# Elektrisch_schema_EasyEDA.net
KiCad netlist of a schematic drawn in EasyEDA
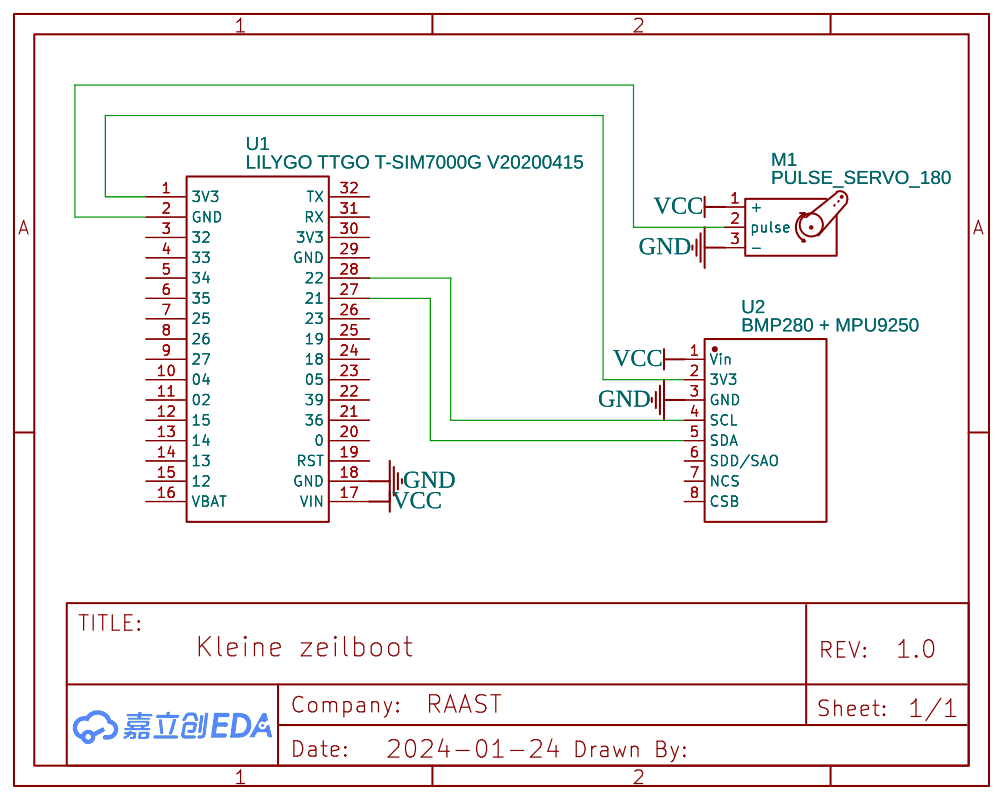
[diagram p0: schematic sheet]

(export (version "E")
  (design (tool "Eeschema 10.0.6"))
  (components
    (comp (ref "M1") (value "PULSE_SERVO_180") (libsource (lib "") (part "PULSE_SERVO_180")))
    (comp (ref "U1")
      (value "LILYGO TTGO T-SIM7000G V20200415")
      (fields (field (name "BOM_Manufacturer Part") "T-SIM7000G"))
      (libsource (lib "") (part "LILYGO TTGO T-SIM7000G V20200415"))
    )
    (comp (ref "U2") (value "BMP280 + MPU9250") (libsource (lib "") (part "BMP280 + MPU9250")))
  )
  (nets
    (net (code "1") (name "GND") (class "Default")
      (node (ref "M1") (pin "3") (pinfunction "-_3") (pintype "unspecified"))
      (node (ref "U1") (pin "18") (pinfunction "GND_18") (pintype "unspecified"))
      (node (ref "U2") (pin "3") (pinfunction "GND_3") (pintype "unspecified"))
    )
    (net (code "2") (name "Net-(M1-pulse)") (class "Default")
      (node (ref "M1") (pin "2") (pinfunction "pulse_2") (pintype "unspecified"))
      (node (ref "U1") (pin "2") (pinfunction "GND_2") (pintype "unspecified"))
    )
    (net (code "3") (name "Net-(U1-21)") (class "Default")
      (node (ref "U1") (pin "27") (pinfunction "21_27") (pintype "unspecified"))
      (node (ref "U2") (pin "5") (pinfunction "SDA_5") (pintype "unspecified"))
    )
    (net (code "4") (name "Net-(U1-22)") (class "Default")
      (node (ref "U1") (pin "28") (pinfunction "22_28") (pintype "unspecified"))
      (node (ref "U2") (pin "4") (pinfunction "SCL_4") (pintype "unspecified"))
    )
    (net (code "5") (name "Net-(U2-3V3)") (class "Default")
      (node (ref "U1") (pin "1") (pinfunction "3V3_1") (pintype "unspecified"))
      (node (ref "U2") (pin "2") (pinfunction "3V3_2") (pintype "unspecified"))
    )
    (net (code "6") (name "VCC") (class "Default")
      (node (ref "M1") (pin "1") (pinfunction "+_1") (pintype "unspecified"))
      (node (ref "U1") (pin "17") (pinfunction "VIN_17") (pintype "unspecified"))
      (node (ref "U2") (pin "1") (pinfunction "Vin_1") (pintype "unspecified"))
    )
    (net (code "7") (name "unconnected-(U1-0-Pad20)") (class "Default")
      (node (ref "U1") (pin "20") (pinfunction "0_20") (pintype "unspecified"))
    )
    (net (code "8") (name "unconnected-(U1-02-Pad11)") (class "Default")
      (node (ref "U1") (pin "11") (pinfunction "02_11") (pintype "unspecified"))
    )
    (net (code "9") (name "unconnected-(U1-3V3-Pad30)") (class "Default")
      (node (ref "U1") (pin "30") (pinfunction "3V3_30") (pintype "unspecified"))
    )
    (net (code "10") (name "unconnected-(U1-04-Pad10)") (class "Default")
      (node (ref "U1") (pin "10") (pinfunction "04_10") (pintype "unspecified"))
    )
    (net (code "11") (name "unconnected-(U1-05-Pad23)") (class "Default")
      (node (ref "U1") (pin "23") (pinfunction "05_23") (pintype "unspecified"))
    )
    (net (code "12") (name "unconnected-(U1-12-Pad15)") (class "Default")
      (node (ref "U1") (pin "15") (pinfunction "12_15") (pintype "unspecified"))
    )
    (net (code "13") (name "unconnected-(U1-13-Pad14)") (class "Default")
      (node (ref "U1") (pin "14") (pinfunction "13_14") (pintype "unspecified"))
    )
    (net (code "14") (name "unconnected-(U1-14-Pad13)") (class "Default")
      (node (ref "U1") (pin "13") (pinfunction "14_13") (pintype "unspecified"))
    )
    (net (code "15") (name "unconnected-(U1-15-Pad12)") (class "Default")
      (node (ref "U1") (pin "12") (pinfunction "15_12") (pintype "unspecified"))
    )
    (net (code "16") (name "unconnected-(U1-18-Pad24)") (class "Default")
      (node (ref "U1") (pin "24") (pinfunction "18_24") (pintype "unspecified"))
    )
    (net (code "17") (name "unconnected-(U1-19-Pad25)") (class "Default")
      (node (ref "U1") (pin "25") (pinfunction "19_25") (pintype "unspecified"))
    )
    (net (code "18") (name "unconnected-(U1-23-Pad26)") (class "Default")
      (node (ref "U1") (pin "26") (pinfunction "23_26") (pintype "unspecified"))
    )
    (net (code "19") (name "unconnected-(U1-25-Pad7)") (class "Default")
      (node (ref "U1") (pin "7") (pinfunction "25_7") (pintype "unspecified"))
    )
    (net (code "20") (name "unconnected-(U1-26-Pad8)") (class "Default")
      (node (ref "U1") (pin "8") (pinfunction "26_8") (pintype "unspecified"))
    )
    (net (code "21") (name "unconnected-(U1-27-Pad9)") (class "Default")
      (node (ref "U1") (pin "9") (pinfunction "27_9") (pintype "unspecified"))
    )
    (net (code "22") (name "unconnected-(U1-32-Pad3)") (class "Default")
      (node (ref "U1") (pin "3") (pinfunction "32_3") (pintype "unspecified"))
    )
    (net (code "23") (name "unconnected-(U1-33-Pad4)") (class "Default")
      (node (ref "U1") (pin "4") (pinfunction "33_4") (pintype "unspecified"))
    )
    (net (code "24") (name "unconnected-(U1-34-Pad5)") (class "Default")
      (node (ref "U1") (pin "5") (pinfunction "34_5") (pintype "unspecified"))
    )
    (net (code "25") (name "unconnected-(U1-35-Pad6)") (class "Default")
      (node (ref "U1") (pin "6") (pinfunction "35_6") (pintype "unspecified"))
    )
    (net (code "26") (name "unconnected-(U1-36-Pad21)") (class "Default")
      (node (ref "U1") (pin "21") (pinfunction "36_21") (pintype "unspecified"))
    )
    (net (code "27") (name "unconnected-(U1-39-Pad22)") (class "Default")
      (node (ref "U1") (pin "22") (pinfunction "39_22") (pintype "unspecified"))
    )
    (net (code "28") (name "unconnected-(U1-GND-Pad29)") (class "Default")
      (node (ref "U1") (pin "29") (pinfunction "GND_29") (pintype "unspecified"))
    )
    (net (code "29") (name "unconnected-(U1-RST-Pad19)") (class "Default")
      (node (ref "U1") (pin "19") (pinfunction "RST_19") (pintype "unspecified"))
    )
    (net (code "30") (name "unconnected-(U1-RX-Pad31)") (class "Default")
      (node (ref "U1") (pin "31") (pinfunction "RX_31") (pintype "unspecified"))
    )
    (net (code "31") (name "unconnected-(U1-TX-Pad32)") (class "Default")
      (node (ref "U1") (pin "32") (pinfunction "TX_32") (pintype "unspecified"))
    )
    (net (code "32") (name "unconnected-(U1-VBAT-Pad16)") (class "Default")
      (node (ref "U1") (pin "16") (pinfunction "VBAT_16") (pintype "unspecified"))
    )
    (net (code "33") (name "unconnected-(U2-CSB-Pad8)") (class "Default")
      (node (ref "U2") (pin "8") (pinfunction "CSB_8") (pintype "unspecified"))
    )
    (net (code "34") (name "unconnected-(U2-NCS-Pad7)") (class "Default")
      (node (ref "U2") (pin "7") (pinfunction "NCS_7") (pintype "unspecified"))
    )
    (net (code "35") (name "unconnected-(U2-SDD{slash}SAO-Pad6)") (class "Default")
      (node (ref "U2") (pin "6") (pinfunction "SDD/SAO_6") (pintype "unspecified"))
    )
  )
)
